# LazuriteBLE_rev1_1.net
KiCad netlist of a schematic drawn in EAGLE
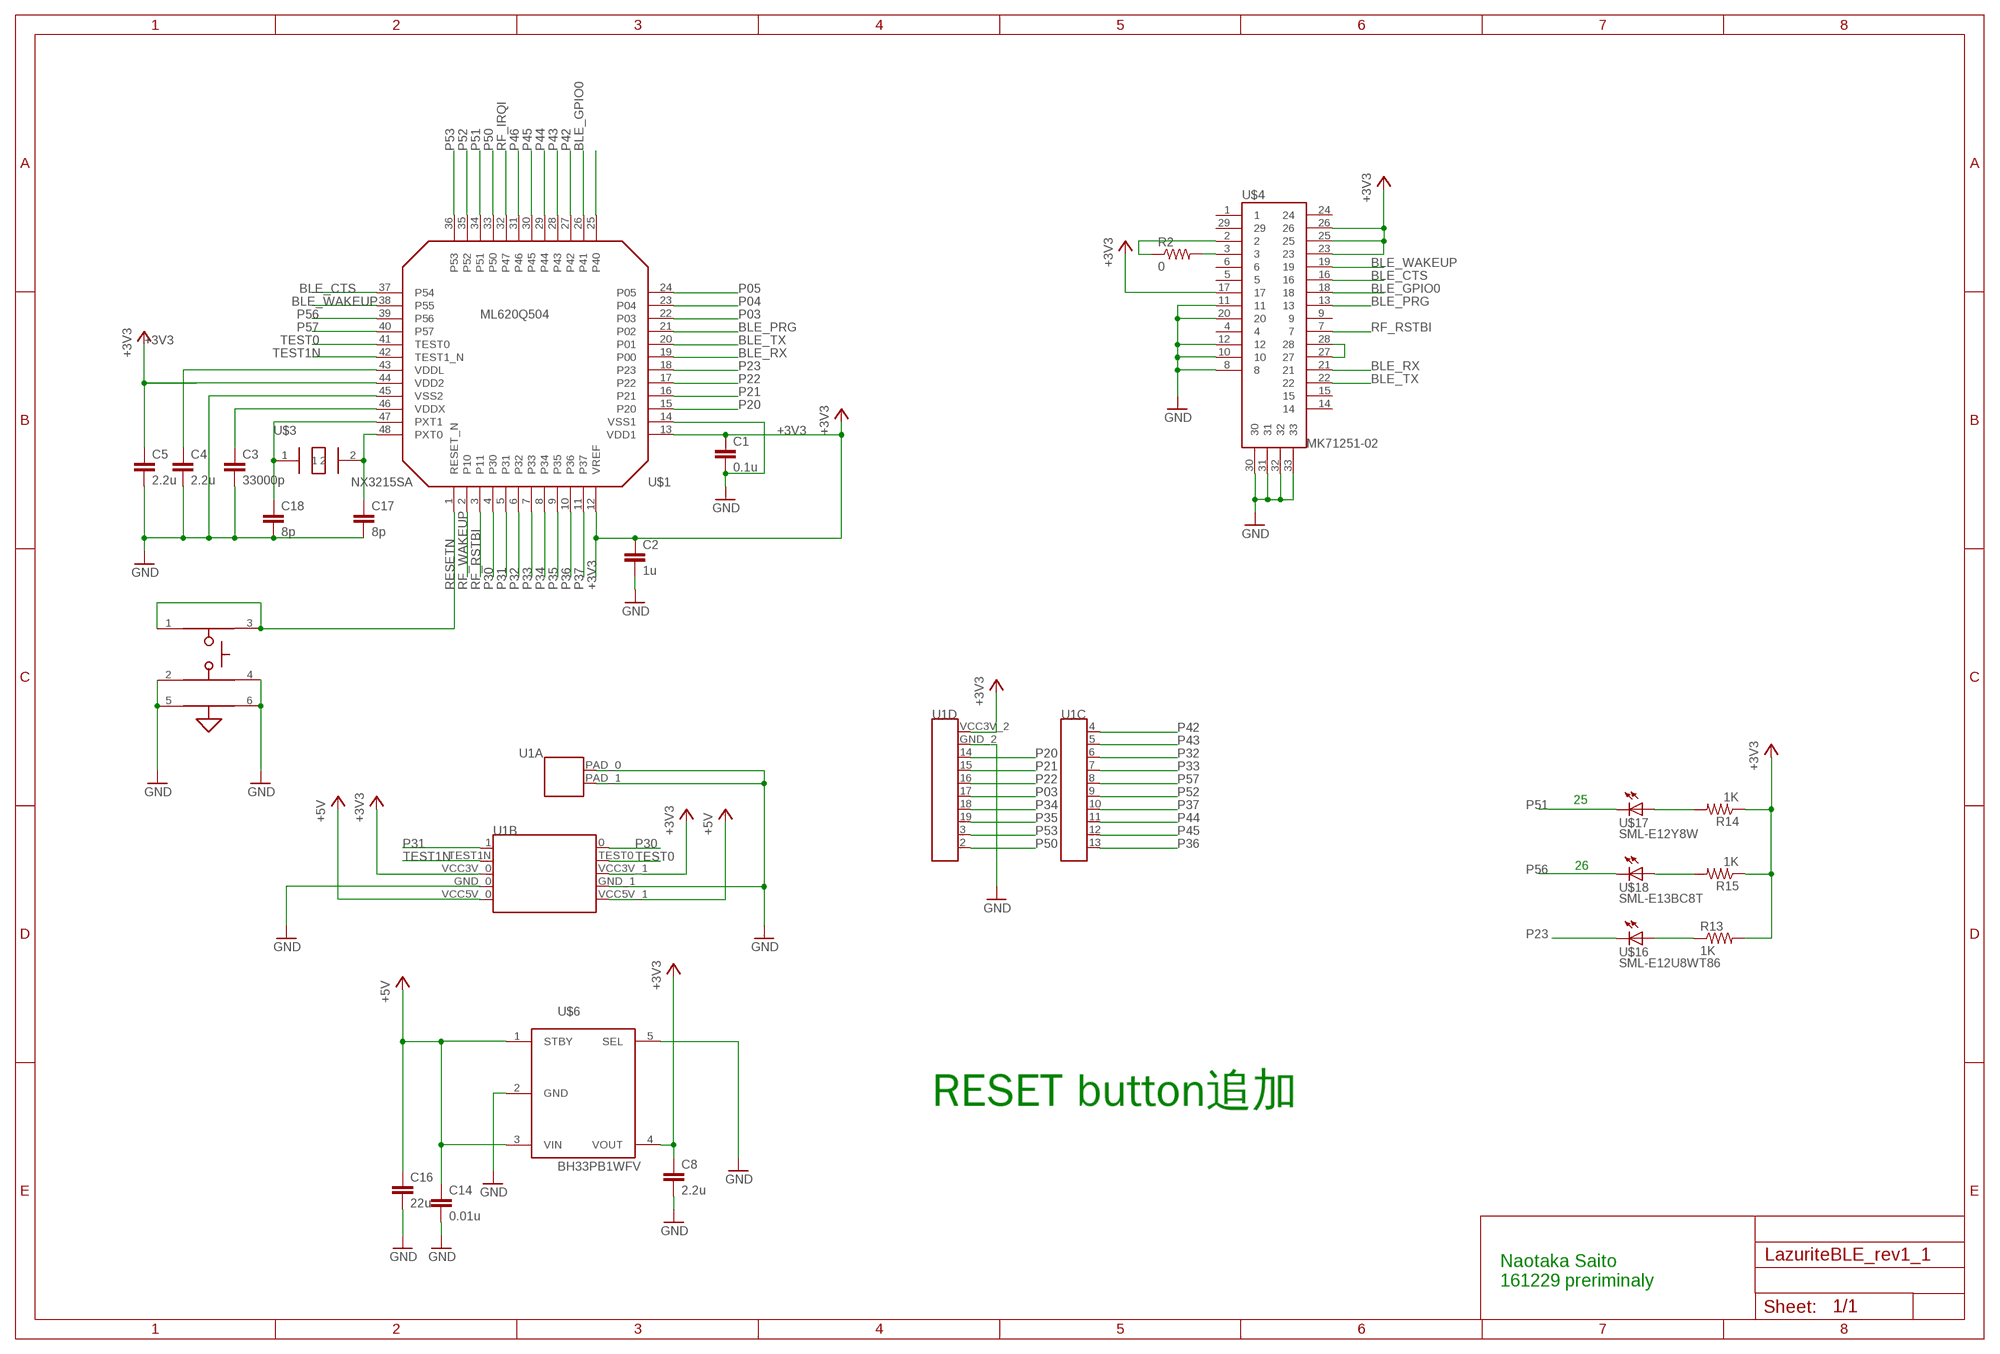
[diagram p0: schematic, sheet 1]

(export (version "E")
  (design (tool "Eeschema 10.0.6"))
  (components
    (comp (ref "C1")
      (value "0.1u")
      (footprint "eagle-import:C0402")
      (libsource (lib "eagle-import") (part "C-EUC0402"))
    )
    (comp (ref "C2")
      (value "1u")
      (footprint "eagle-import:C0402")
      (libsource (lib "eagle-import") (part "C-EUC0402"))
    )
    (comp (ref "C3")
      (value "33000p")
      (footprint "eagle-import:C0402")
      (libsource (lib "eagle-import") (part "C-EUC0402"))
    )
    (comp (ref "C4")
      (value "2.2u")
      (footprint "eagle-import:C0402")
      (libsource (lib "eagle-import") (part "C-EUC0402"))
    )
    (comp (ref "C5")
      (value "2.2u")
      (footprint "eagle-import:C0402")
      (libsource (lib "eagle-import") (part "C-EUC0402"))
    )
    (comp (ref "C8")
      (value "2.2u")
      (footprint "eagle-import:C0402")
      (libsource (lib "eagle-import") (part "C-EUC0402"))
    )
    (comp (ref "C14")
      (value "0.01u")
      (footprint "eagle-import:C0402")
      (libsource (lib "eagle-import") (part "C-EUC0402"))
    )
    (comp (ref "C16")
      (value "22u")
      (footprint "eagle-import:C1206")
      (libsource (lib "eagle-import") (part "C-EUC1206"))
    )
    (comp (ref "C17")
      (value "8p")
      (footprint "eagle-import:C0402")
      (libsource (lib "eagle-import") (part "C-EUC0402"))
    )
    (comp (ref "C18")
      (value "8p")
      (footprint "eagle-import:C0402")
      (libsource (lib "eagle-import") (part "C-EUC0402"))
    )
    (comp (ref "R2")
      (value "0")
      (footprint "eagle-import:R0402")
      (libsource (lib "eagle-import") (part "R-US_R0402"))
    )
    (comp (ref "R13")
      (value "1K")
      (footprint "eagle-import:R0402")
      (libsource (lib "eagle-import") (part "R-US_R0402"))
    )
    (comp (ref "R14")
      (value "1K")
      (footprint "eagle-import:R0402")
      (libsource (lib "eagle-import") (part "R-US_R0402"))
    )
    (comp (ref "R15")
      (value "1K")
      (footprint "eagle-import:R0402")
      (libsource (lib "eagle-import") (part "R-US_R0402"))
    )
    (comp (ref "SW1")
      (value "SKSGACE010")
      (footprint "eagle-import:SKSGACE010")
      (libsource (lib "eagle-import") (part "SKSGACE010"))
    )
    (comp (ref "U$1")
      (value "ML620Q504")
      (footprint "eagle-import:ML620Q504")
      (libsource (lib "eagle-import") (part "ML620Q504"))
    )
    (comp (ref "U$3")
      (value "NX3215SA")
      (footprint "eagle-import:NX3215SA-32,768K-SFD-MUA-14")
      (libsource (lib "eagle-import") (part "NX3215SA"))
    )
    (comp (ref "U$4")
      (value "MK71251-02")
      (footprint "eagle-import:MK71251-02")
      (libsource (lib "eagle-import") (part "MK71251-02"))
    )
    (comp (ref "U$6")
      (value "BH33PB1WFV")
      (footprint "eagle-import:HVSOF5")
      (libsource (lib "eagle-import") (part "BHXXPB1WFV"))
    )
    (comp (ref "U$16")
      (value "SML-E12U8WT86")
      (footprint "eagle-import:SML-E1X")
      (libsource (lib "eagle-import") (part "SML-E1X"))
    )
    (comp (ref "U$17")
      (value "SML-E12Y8W")
      (footprint "eagle-import:SML-E1X")
      (libsource (lib "eagle-import") (part "SML-E1X"))
    )
    (comp (ref "U$18")
      (value "SML-E13BC8T")
      (footprint "eagle-import:SML-E1X")
      (libsource (lib "eagle-import") (part "SML-E1X"))
    )
    (comp (ref "U1")
      (value "LAZURITE920J")
      (footprint "eagle-import:LAZURITE920J2")
      (libsource (lib "eagle-import") (part "LAZURITE920J"))
    )
  )
  (nets
    (net (code "1") (name "+3V3") (class "Default")
      (node (ref "C1") (pin "1") (pinfunction "1_1") (pintype "passive"))
      (node (ref "C2") (pin "1") (pinfunction "1_1") (pintype "passive"))
      (node (ref "C5") (pin "1") (pinfunction "1_1") (pintype "passive"))
      (node (ref "C8") (pin "1") (pinfunction "1_1") (pintype "passive"))
      (node (ref "R13") (pin "2") (pinfunction "2_2") (pintype "passive"))
      (node (ref "R14") (pin "1") (pinfunction "1_1") (pintype "passive"))
      (node (ref "R15") (pin "1") (pinfunction "1_1") (pintype "passive"))
      (node (ref "U$1") (pin "12") (pinfunction "VREF_12") (pintype "bidirectional"))
      (node (ref "U$1") (pin "13") (pinfunction "VDD1_13") (pintype "bidirectional"))
      (node (ref "U$1") (pin "44") (pinfunction "VDD2_44") (pintype "bidirectional"))
      (node (ref "U$4") (pin "17") (pinfunction "17_17") (pintype "power_in"))
      (node (ref "U$4") (pin "23") (pinfunction "23_23") (pintype "bidirectional"))
      (node (ref "U$4") (pin "25") (pinfunction "25_25") (pintype "bidirectional"))
      (node (ref "U$4") (pin "26") (pinfunction "26_26") (pintype "bidirectional"))
      (node (ref "U$6") (pin "4") (pinfunction "VOUT_4") (pintype "bidirectional"))
      (node (ref "U1") (pin "VCC3V_0") (pinfunction "VCC3V_0_VCC3V_0") (pintype "passive"))
      (node (ref "U1") (pin "VCC3V_1") (pinfunction "VCC3V_1_VCC3V_1") (pintype "passive"))
      (node (ref "U1") (pin "VCC3V_2") (pinfunction "VCC3V_2_VCC3V_2") (pintype "passive"))
    )
    (net (code "2") (name "+5V") (class "Default")
      (node (ref "C14") (pin "1") (pinfunction "1_1") (pintype "passive"))
      (node (ref "C16") (pin "1") (pinfunction "1_1") (pintype "passive"))
      (node (ref "U$6") (pin "1") (pinfunction "STBY_1") (pintype "bidirectional"))
      (node (ref "U$6") (pin "3") (pinfunction "VIN_3") (pintype "bidirectional"))
      (node (ref "U1") (pin "VCC5V_0") (pinfunction "VCC5V_0_VCC5V_0") (pintype "passive"))
      (node (ref "U1") (pin "VCC5V_1") (pinfunction "VCC5V_1_VCC5V_1") (pintype "passive"))
    )
    (net (code "3") (name "/BLE_CTS") (class "Default")
      (node (ref "U$1") (pin "37") (pinfunction "P54_37") (pintype "bidirectional"))
      (node (ref "U$4") (pin "16") (pinfunction "16_16") (pintype "bidirectional"))
    )
    (net (code "4") (name "/BLE_GPIO0") (class "Default")
      (node (ref "U$1") (pin "26") (pinfunction "P41_26") (pintype "bidirectional"))
      (node (ref "U$4") (pin "18") (pinfunction "18_18") (pintype "bidirectional"))
    )
    (net (code "5") (name "/BLE_PRG") (class "Default")
      (node (ref "U$1") (pin "21") (pinfunction "P02_21") (pintype "bidirectional"))
      (node (ref "U$4") (pin "13") (pinfunction "13_13") (pintype "bidirectional"))
    )
    (net (code "6") (name "/BLE_RX") (class "Default")
      (node (ref "U$1") (pin "19") (pinfunction "P00_19") (pintype "bidirectional"))
      (node (ref "U$4") (pin "21") (pinfunction "21_21") (pintype "bidirectional"))
    )
    (net (code "7") (name "/BLE_TX") (class "Default")
      (node (ref "U$1") (pin "20") (pinfunction "P01_20") (pintype "bidirectional"))
      (node (ref "U$4") (pin "22") (pinfunction "22_22") (pintype "bidirectional"))
    )
    (net (code "8") (name "/BLE_WAKEUP") (class "Default")
      (node (ref "U$1") (pin "38") (pinfunction "P55_38") (pintype "bidirectional"))
      (node (ref "U$4") (pin "19") (pinfunction "19_19") (pintype "input"))
    )
    (net (code "9") (name "/P03") (class "Default")
      (node (ref "U$1") (pin "22") (pinfunction "P03_22") (pintype "bidirectional"))
      (node (ref "U1") (pin "17") (pinfunction "17_17") (pintype "passive"))
    )
    (net (code "10") (name "/P04") (class "Default")
      (node (ref "U$1") (pin "23") (pinfunction "P04_23") (pintype "bidirectional"))
    )
    (net (code "11") (name "/P05") (class "Default")
      (node (ref "U$1") (pin "24") (pinfunction "P05_24") (pintype "bidirectional"))
    )
    (net (code "12") (name "/P20") (class "Default")
      (node (ref "U$1") (pin "15") (pinfunction "P20_15") (pintype "bidirectional"))
      (node (ref "U1") (pin "14") (pinfunction "14_14") (pintype "passive"))
    )
    (net (code "13") (name "/P21") (class "Default")
      (node (ref "U$1") (pin "16") (pinfunction "P21_16") (pintype "bidirectional"))
      (node (ref "U1") (pin "15") (pinfunction "15_15") (pintype "passive"))
    )
    (net (code "14") (name "/P22") (class "Default")
      (node (ref "U$1") (pin "17") (pinfunction "P22_17") (pintype "bidirectional"))
      (node (ref "U1") (pin "16") (pinfunction "16_16") (pintype "passive"))
    )
    (net (code "15") (name "/P23") (class "Default")
      (node (ref "U$1") (pin "18") (pinfunction "P23_18") (pintype "bidirectional"))
      (node (ref "U$16") (pin "C") (pinfunction "C_C") (pintype "passive"))
    )
    (net (code "16") (name "/P30") (class "Default")
      (node (ref "U$1") (pin "4") (pinfunction "P30_4") (pintype "bidirectional"))
      (node (ref "U1") (pin "0") (pinfunction "0_0") (pintype "passive"))
    )
    (net (code "17") (name "/P31") (class "Default")
      (node (ref "U$1") (pin "5") (pinfunction "P31_5") (pintype "bidirectional"))
      (node (ref "U1") (pin "1") (pinfunction "1_1") (pintype "passive"))
    )
    (net (code "18") (name "/P32") (class "Default")
      (node (ref "U$1") (pin "6") (pinfunction "P32_6") (pintype "bidirectional"))
      (node (ref "U1") (pin "6") (pinfunction "6_6") (pintype "passive"))
    )
    (net (code "19") (name "/P33") (class "Default")
      (node (ref "U$1") (pin "7") (pinfunction "P33_7") (pintype "bidirectional"))
      (node (ref "U1") (pin "7") (pinfunction "7_7") (pintype "passive"))
    )
    (net (code "20") (name "/P34") (class "Default")
      (node (ref "U$1") (pin "8") (pinfunction "P34_8") (pintype "bidirectional"))
      (node (ref "U1") (pin "18") (pinfunction "18_18") (pintype "passive"))
    )
    (net (code "21") (name "/P35") (class "Default")
      (node (ref "U$1") (pin "9") (pinfunction "P35_9") (pintype "bidirectional"))
      (node (ref "U1") (pin "19") (pinfunction "19_19") (pintype "passive"))
    )
    (net (code "22") (name "/P36") (class "Default")
      (node (ref "U$1") (pin "10") (pinfunction "P36_10") (pintype "bidirectional"))
      (node (ref "U1") (pin "13") (pinfunction "13_13") (pintype "passive"))
    )
    (net (code "23") (name "/P37") (class "Default")
      (node (ref "U$1") (pin "11") (pinfunction "P37_11") (pintype "bidirectional"))
      (node (ref "U1") (pin "10") (pinfunction "10_10") (pintype "passive"))
    )
    (net (code "24") (name "/P42") (class "Default")
      (node (ref "U$1") (pin "27") (pinfunction "P42_27") (pintype "bidirectional"))
      (node (ref "U1") (pin "4") (pinfunction "4_4") (pintype "passive"))
    )
    (net (code "25") (name "/P43") (class "Default")
      (node (ref "U$1") (pin "28") (pinfunction "P43_28") (pintype "bidirectional"))
      (node (ref "U1") (pin "5") (pinfunction "5_5") (pintype "passive"))
    )
    (net (code "26") (name "/P44") (class "Default")
      (node (ref "U$1") (pin "29") (pinfunction "P44_29") (pintype "bidirectional"))
      (node (ref "U1") (pin "11") (pinfunction "11_11") (pintype "passive"))
    )
    (net (code "27") (name "/P45") (class "Default")
      (node (ref "U$1") (pin "30") (pinfunction "P45_30") (pintype "bidirectional"))
      (node (ref "U1") (pin "12") (pinfunction "12_12") (pintype "passive"))
    )
    (net (code "28") (name "/P46") (class "Default")
      (node (ref "U$1") (pin "31") (pinfunction "P46_31") (pintype "bidirectional"))
    )
    (net (code "29") (name "/P50") (class "Default")
      (node (ref "U$1") (pin "33") (pinfunction "P50_33") (pintype "bidirectional"))
      (node (ref "U1") (pin "2") (pinfunction "2_2") (pintype "passive"))
    )
    (net (code "30") (name "/P51") (class "Default")
      (node (ref "U$1") (pin "34") (pinfunction "P51_34") (pintype "bidirectional"))
      (node (ref "U$17") (pin "C") (pinfunction "C_C") (pintype "passive"))
    )
    (net (code "31") (name "/P52") (class "Default")
      (node (ref "U$1") (pin "35") (pinfunction "P52_35") (pintype "bidirectional"))
      (node (ref "U1") (pin "9") (pinfunction "9_9") (pintype "passive"))
    )
    (net (code "32") (name "/P53") (class "Default")
      (node (ref "U$1") (pin "36") (pinfunction "P53_36") (pintype "bidirectional"))
      (node (ref "U1") (pin "3") (pinfunction "3_3") (pintype "passive"))
    )
    (net (code "33") (name "/P56") (class "Default")
      (node (ref "U$1") (pin "39") (pinfunction "P56_39") (pintype "bidirectional"))
      (node (ref "U$18") (pin "C") (pinfunction "C_C") (pintype "passive"))
    )
    (net (code "34") (name "/P57") (class "Default")
      (node (ref "U$1") (pin "40") (pinfunction "P57_40") (pintype "bidirectional"))
      (node (ref "U1") (pin "8") (pinfunction "8_8") (pintype "passive"))
    )
    (net (code "35") (name "/RESETN") (class "Default")
      (node (ref "SW1") (pin "1") (pinfunction "1_1") (pintype "bidirectional"))
      (node (ref "SW1") (pin "3") (pinfunction "3_3") (pintype "bidirectional"))
      (node (ref "U$1") (pin "1") (pinfunction "RESET_N_1") (pintype "bidirectional"))
    )
    (net (code "36") (name "/RF_IRQI") (class "Default")
      (node (ref "U$1") (pin "32") (pinfunction "P47_32") (pintype "bidirectional"))
    )
    (net (code "37") (name "/RF_RSTBI") (class "Default")
      (node (ref "U$1") (pin "3") (pinfunction "P11_3") (pintype "bidirectional"))
      (node (ref "U$4") (pin "7") (pinfunction "7_7") (pintype "input"))
    )
    (net (code "38") (name "/RF_WAKEUP") (class "Default")
      (node (ref "U$1") (pin "2") (pinfunction "P10_2") (pintype "bidirectional"))
    )
    (net (code "39") (name "/TEST0") (class "Default")
      (node (ref "U$1") (pin "41") (pinfunction "TEST0_41") (pintype "bidirectional"))
      (node (ref "U1") (pin "TEST0") (pinfunction "TEST0_TEST0") (pintype "passive"))
    )
    (net (code "40") (name "/TEST1N") (class "Default")
      (node (ref "U$1") (pin "42") (pinfunction "TEST1_N_42") (pintype "bidirectional"))
      (node (ref "U1") (pin "TEST1N") (pinfunction "TEST1N_TEST1N") (pintype "passive"))
    )
    (net (code "41") (name "GND") (class "Default")
      (node (ref "C1") (pin "2") (pinfunction "2_2") (pintype "passive"))
      (node (ref "C14") (pin "2") (pinfunction "2_2") (pintype "passive"))
      (node (ref "C16") (pin "2") (pinfunction "2_2") (pintype "passive"))
      (node (ref "C17") (pin "2") (pinfunction "2_2") (pintype "passive"))
      (node (ref "C18") (pin "2") (pinfunction "2_2") (pintype "passive"))
      (node (ref "C2") (pin "2") (pinfunction "2_2") (pintype "passive"))
      (node (ref "C3") (pin "2") (pinfunction "2_2") (pintype "passive"))
      (node (ref "C4") (pin "2") (pinfunction "2_2") (pintype "passive"))
      (node (ref "C5") (pin "2") (pinfunction "2_2") (pintype "passive"))
      (node (ref "C8") (pin "2") (pinfunction "2_2") (pintype "passive"))
      (node (ref "SW1") (pin "2") (pinfunction "2_2") (pintype "bidirectional"))
      (node (ref "SW1") (pin "4") (pinfunction "4_4") (pintype "bidirectional"))
      (node (ref "SW1") (pin "5") (pinfunction "5_5") (pintype "power_in"))
      (node (ref "SW1") (pin "6") (pinfunction "6_6") (pintype "power_in"))
      (node (ref "U$1") (pin "14") (pinfunction "VSS1_14") (pintype "bidirectional"))
      (node (ref "U$1") (pin "45") (pinfunction "VSS2_45") (pintype "bidirectional"))
      (node (ref "U$4") (pin "10") (pinfunction "10_10") (pintype "input"))
      (node (ref "U$4") (pin "11") (pinfunction "11_11") (pintype "bidirectional"))
      (node (ref "U$4") (pin "12") (pinfunction "12_12") (pintype "input"))
      (node (ref "U$4") (pin "20") (pinfunction "20_20") (pintype "bidirectional"))
      (node (ref "U$4") (pin "30") (pinfunction "30_30") (pintype "power_in"))
      (node (ref "U$4") (pin "31") (pinfunction "31_31") (pintype "power_in"))
      (node (ref "U$4") (pin "32") (pinfunction "32_32") (pintype "power_in"))
      (node (ref "U$4") (pin "33") (pinfunction "33_33") (pintype "power_in"))
      (node (ref "U$4") (pin "8") (pinfunction "8_8") (pintype "input"))
      (node (ref "U$6") (pin "2") (pinfunction "GND_2") (pintype "bidirectional"))
      (node (ref "U$6") (pin "5") (pinfunction "SEL_5") (pintype "bidirectional"))
      (node (ref "U1") (pin "GND_0") (pinfunction "GND_0_GND_0") (pintype "passive"))
      (node (ref "U1") (pin "GND_1") (pinfunction "GND_1_GND_1") (pintype "passive"))
      (node (ref "U1") (pin "GND_2") (pinfunction "GND_2_GND_2") (pintype "passive"))
      (node (ref "U1") (pin "PAD_0") (pinfunction "PAD_0_PAD_0") (pintype "passive"))
      (node (ref "U1") (pin "PAD_1") (pinfunction "PAD_1_PAD_1") (pintype "passive"))
    )
    (net (code "42") (name "Net-(R2-Pad1)") (class "Default")
      (node (ref "R2") (pin "1") (pinfunction "1_1") (pintype "passive"))
      (node (ref "U$4") (pin "2") (pinfunction "2_2") (pintype "input"))
    )
    (net (code "43") (name "Net-(R2-Pad2)") (class "Default")
      (node (ref "R2") (pin "2") (pinfunction "2_2") (pintype "passive"))
      (node (ref "U$4") (pin "3") (pinfunction "3_3") (pintype "bidirectional"))
    )
    (net (code "44") (name "Net-(R13-Pad1)") (class "Default")
      (node (ref "R13") (pin "1") (pinfunction "1_1") (pintype "passive"))
      (node (ref "U$16") (pin "A") (pinfunction "A_A") (pintype "passive"))
    )
    (net (code "45") (name "Net-(R14-Pad2)") (class "Default")
      (node (ref "R14") (pin "2") (pinfunction "2_2") (pintype "passive"))
      (node (ref "U$17") (pin "A") (pinfunction "A_A") (pintype "passive"))
    )
    (net (code "46") (name "Net-(R15-Pad2)") (class "Default")
      (node (ref "R15") (pin "2") (pinfunction "2_2") (pintype "passive"))
      (node (ref "U$18") (pin "A") (pinfunction "A_A") (pintype "passive"))
    )
    (net (code "47") (name "Net-(U$1-PXT0)") (class "Default")
      (node (ref "C17") (pin "1") (pinfunction "1_1") (pintype "passive"))
      (node (ref "U$1") (pin "48") (pinfunction "PXT0_48") (pintype "bidirectional"))
      (node (ref "U$3") (pin "2") (pinfunction "2_2") (pintype "bidirectional"))
    )
    (net (code "48") (name "Net-(U$1-PXT1)") (class "Default")
      (node (ref "C18") (pin "1") (pinfunction "1_1") (pintype "passive"))
      (node (ref "U$1") (pin "47") (pinfunction "PXT1_47") (pintype "bidirectional"))
      (node (ref "U$3") (pin "1") (pinfunction "1_1") (pintype "bidirectional"))
    )
    (net (code "49") (name "Net-(U$1-VDDL)") (class "Default")
      (node (ref "C4") (pin "1") (pinfunction "1_1") (pintype "passive"))
      (node (ref "U$1") (pin "43") (pinfunction "VDDL_43") (pintype "bidirectional"))
    )
    (net (code "50") (name "Net-(U$1-VDDX)") (class "Default")
      (node (ref "C3") (pin "1") (pinfunction "1_1") (pintype "passive"))
      (node (ref "U$1") (pin "46") (pinfunction "VDDX_46") (pintype "bidirectional"))
    )
    (net (code "51") (name "Net-(U$4-Pad27)") (class "Default")
      (node (ref "U$4") (pin "27") (pinfunction "27_27") (pintype "bidirectional"))
      (node (ref "U$4") (pin "28") (pinfunction "28_28") (pintype "bidirectional"))
    )
    (net (code "52") (name "unconnected-(U$1-P40-Pad25)") (class "Default")
      (node (ref "U$1") (pin "25") (pinfunction "P40_25") (pintype "bidirectional"))
    )
    (net (code "53") (name "unconnected-(U$4-Pad1)") (class "Default")
      (node (ref "U$4") (pin "1") (pinfunction "1_1") (pintype "no_connect"))
    )
    (net (code "54") (name "unconnected-(U$4-Pad4)") (class "Default")
      (node (ref "U$4") (pin "4") (pinfunction "4_4") (pintype "bidirectional"))
    )
    (net (code "55") (name "unconnected-(U$4-Pad5)") (class "Default")
      (node (ref "U$4") (pin "5") (pinfunction "5_5") (pintype "bidirectional"))
    )
    (net (code "56") (name "unconnected-(U$4-Pad6)") (class "Default")
      (node (ref "U$4") (pin "6") (pinfunction "6_6") (pintype "bidirectional"))
    )
    (net (code "57") (name "unconnected-(U$4-Pad9)") (class "Default")
      (node (ref "U$4") (pin "9") (pinfunction "9_9") (pintype "bidirectional"))
    )
    (net (code "58") (name "unconnected-(U$4-Pad14)") (class "Default")
      (node (ref "U$4") (pin "14") (pinfunction "14_14") (pintype "bidirectional"))
    )
    (net (code "59") (name "unconnected-(U$4-Pad15)") (class "Default")
      (node (ref "U$4") (pin "15") (pinfunction "15_15") (pintype "bidirectional"))
    )
    (net (code "60") (name "unconnected-(U$4-Pad24)") (class "Default")
      (node (ref "U$4") (pin "24") (pinfunction "24_24") (pintype "bidirectional"))
    )
    (net (code "61") (name "unconnected-(U$4-Pad29)") (class "Default")
      (node (ref "U$4") (pin "29") (pinfunction "29_29") (pintype "no_connect"))
    )
  )
)
